# fastkey_-_v1_1.net
KiCad netlist of a schematic drawn in EAGLE
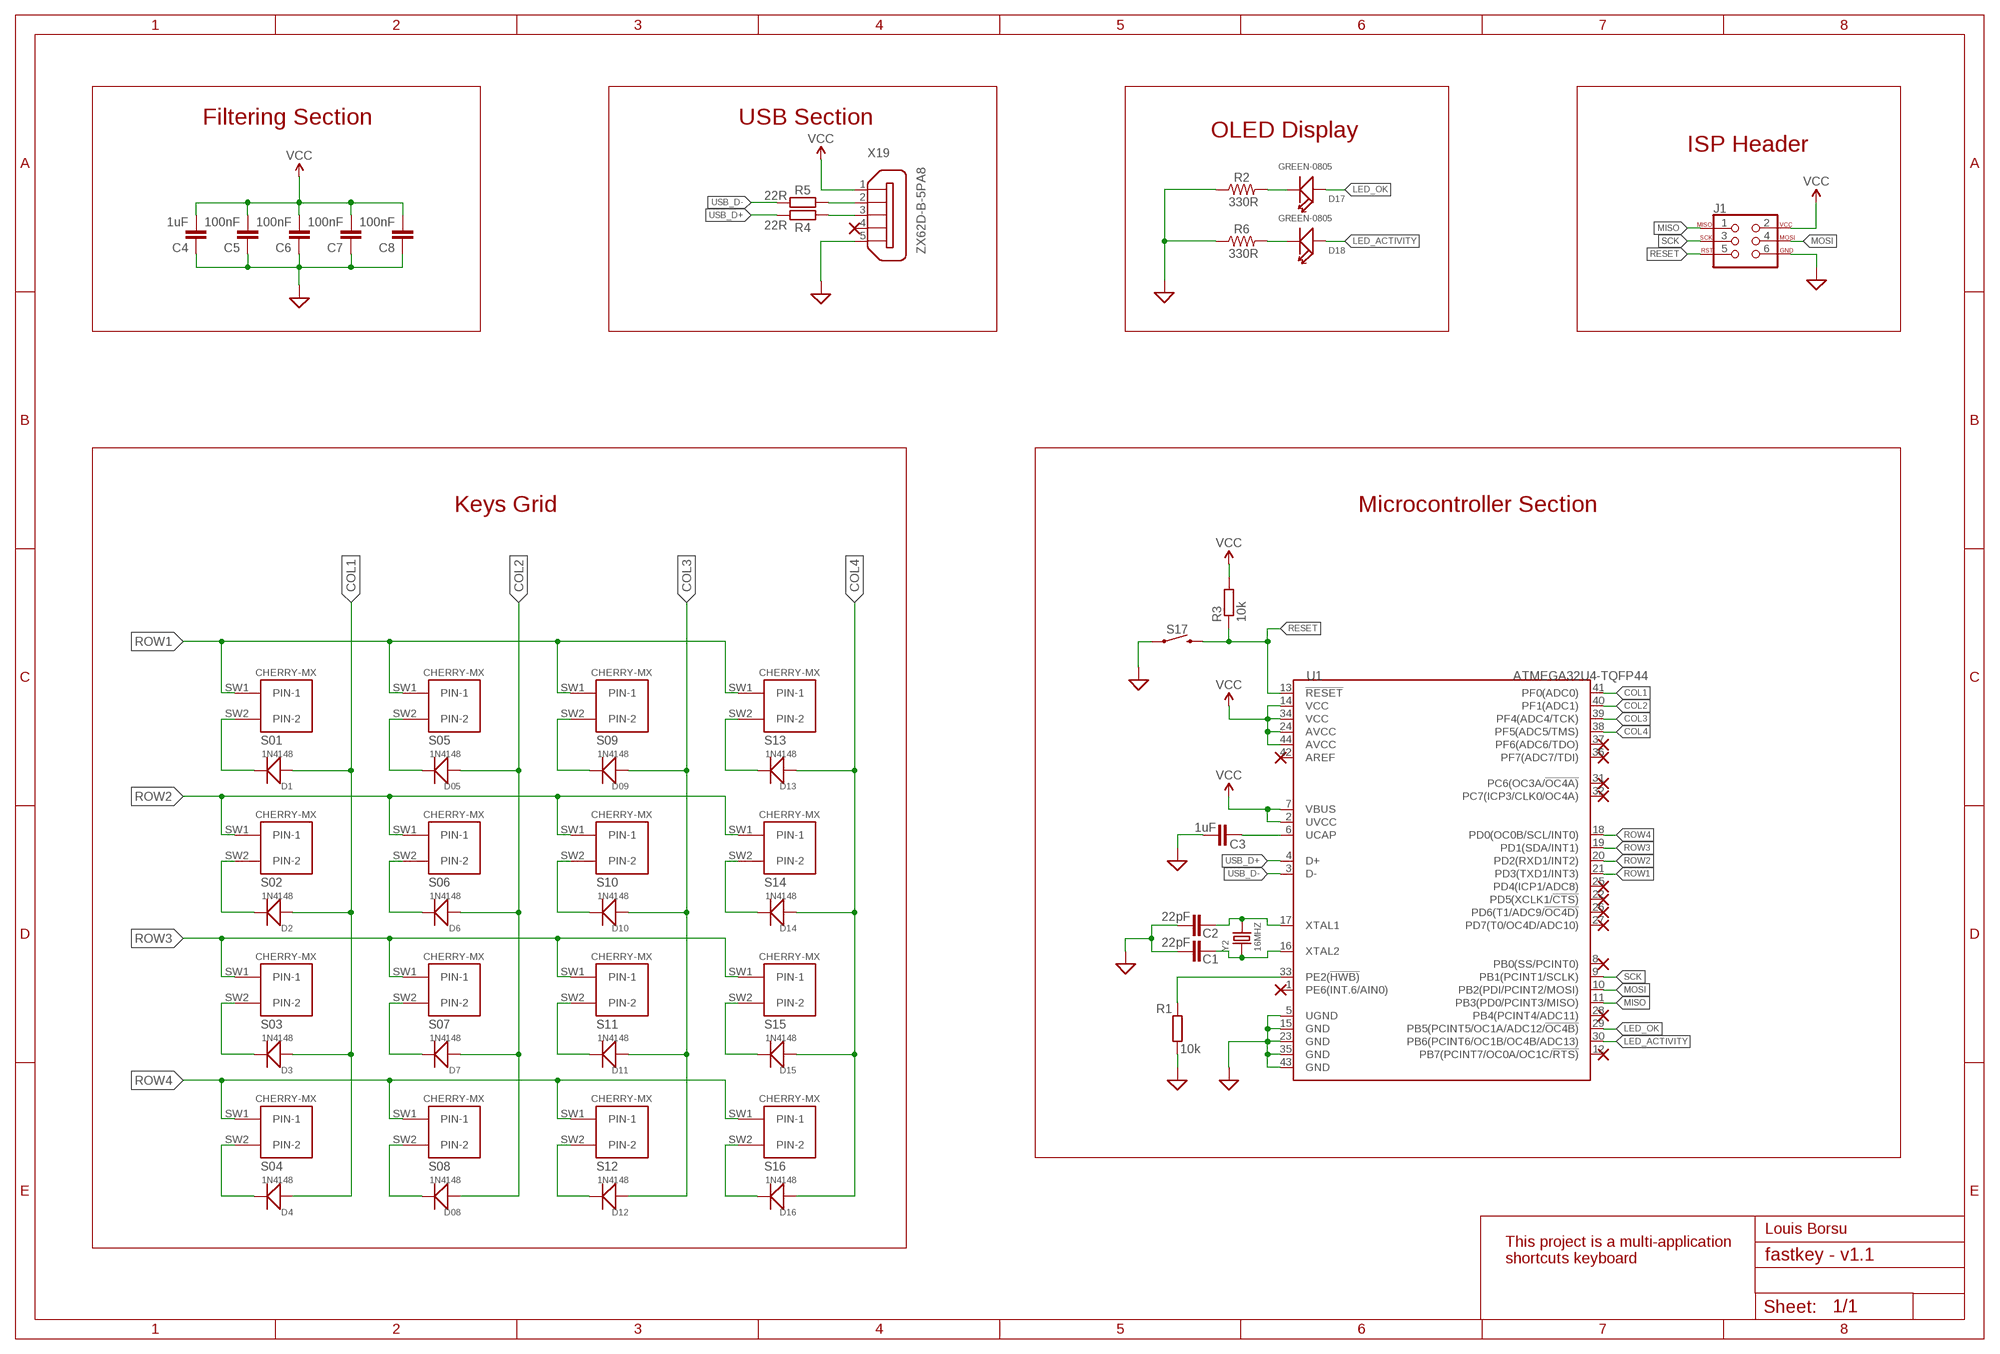
[diagram p0: schematic, sheet 1]

(export (version "E")
  (design (tool "Eeschema 10.0.6"))
  (components
    (comp (ref "C1")
      (value "22pF")
      (footprint "eagle-import:RESC0805_M")
      (libsource (lib "eagle-import") (part "CAPACITOR_0805_M"))
    )
    (comp (ref "C2")
      (value "22pF")
      (footprint "eagle-import:RESC0805_M")
      (libsource (lib "eagle-import") (part "CAPACITOR_0805_M"))
    )
    (comp (ref "C3")
      (value "1uF")
      (footprint "eagle-import:RESC0805_M")
      (libsource (lib "eagle-import") (part "CAPACITOR_0805_M"))
    )
    (comp (ref "C4")
      (value "1uF")
      (footprint "eagle-import:RESC0805_M")
      (libsource (lib "eagle-import") (part "CAPACITOR_0805_M"))
    )
    (comp (ref "C5")
      (value "100nF")
      (footprint "eagle-import:RESC0805_M")
      (libsource (lib "eagle-import") (part "CAPACITOR_0805_M"))
    )
    (comp (ref "C6")
      (value "100nF")
      (footprint "eagle-import:RESC0805_M")
      (libsource (lib "eagle-import") (part "CAPACITOR_0805_M"))
    )
    (comp (ref "C7")
      (value "100nF")
      (footprint "eagle-import:RESC0805_M")
      (libsource (lib "eagle-import") (part "CAPACITOR_0805_M"))
    )
    (comp (ref "C8")
      (value "100nF")
      (footprint "eagle-import:RESC0805_M")
      (libsource (lib "eagle-import") (part "CAPACITOR_0805_M"))
    )
    (comp (ref "D1")
      (value "1N4148")
      (footprint "eagle-import:LL-34")
      (libsource (lib "eagle-import") (part "SMD-DIODE-SWITCH-1N4148(LL-34)"))
    )
    (comp (ref "D2")
      (value "1N4148")
      (footprint "eagle-import:LL-34")
      (libsource (lib "eagle-import") (part "SMD-DIODE-SWITCH-1N4148(LL-34)"))
    )
    (comp (ref "D3")
      (value "1N4148")
      (footprint "eagle-import:LL-34")
      (libsource (lib "eagle-import") (part "SMD-DIODE-SWITCH-1N4148(LL-34)"))
    )
    (comp (ref "D4")
      (value "1N4148")
      (footprint "eagle-import:LL-34")
      (libsource (lib "eagle-import") (part "SMD-DIODE-SWITCH-1N4148(LL-34)"))
    )
    (comp (ref "D05")
      (value "1N4148")
      (footprint "eagle-import:LL-34")
      (libsource (lib "eagle-import") (part "SMD-DIODE-SWITCH-1N4148(LL-34)"))
    )
    (comp (ref "D6")
      (value "1N4148")
      (footprint "eagle-import:LL-34")
      (libsource (lib "eagle-import") (part "SMD-DIODE-SWITCH-1N4148(LL-34)"))
    )
    (comp (ref "D7")
      (value "1N4148")
      (footprint "eagle-import:LL-34")
      (libsource (lib "eagle-import") (part "SMD-DIODE-SWITCH-1N4148(LL-34)"))
    )
    (comp (ref "D08")
      (value "1N4148")
      (footprint "eagle-import:LL-34")
      (libsource (lib "eagle-import") (part "SMD-DIODE-SWITCH-1N4148(LL-34)"))
    )
    (comp (ref "D09")
      (value "1N4148")
      (footprint "eagle-import:LL-34")
      (libsource (lib "eagle-import") (part "SMD-DIODE-SWITCH-1N4148(LL-34)"))
    )
    (comp (ref "D10")
      (value "1N4148")
      (footprint "eagle-import:LL-34")
      (libsource (lib "eagle-import") (part "SMD-DIODE-SWITCH-1N4148(LL-34)"))
    )
    (comp (ref "D11")
      (value "1N4148")
      (footprint "eagle-import:LL-34")
      (libsource (lib "eagle-import") (part "SMD-DIODE-SWITCH-1N4148(LL-34)"))
    )
    (comp (ref "D12")
      (value "1N4148")
      (footprint "eagle-import:LL-34")
      (libsource (lib "eagle-import") (part "SMD-DIODE-SWITCH-1N4148(LL-34)"))
    )
    (comp (ref "D13")
      (value "1N4148")
      (footprint "eagle-import:LL-34")
      (libsource (lib "eagle-import") (part "SMD-DIODE-SWITCH-1N4148(LL-34)"))
    )
    (comp (ref "D14")
      (value "1N4148")
      (footprint "eagle-import:LL-34")
      (libsource (lib "eagle-import") (part "SMD-DIODE-SWITCH-1N4148(LL-34)"))
    )
    (comp (ref "D15")
      (value "1N4148")
      (footprint "eagle-import:LL-34")
      (libsource (lib "eagle-import") (part "SMD-DIODE-SWITCH-1N4148(LL-34)"))
    )
    (comp (ref "D16")
      (value "1N4148")
      (footprint "eagle-import:LL-34")
      (libsource (lib "eagle-import") (part "SMD-DIODE-SWITCH-1N4148(LL-34)"))
    )
    (comp (ref "D17")
      (value "GREEN-0805")
      (footprint "eagle-import:LED-0805")
      (fields (field (name "MPN") "17-215SYGC/S530-E2/TR8"))
      (libsource (lib "eagle-import") (part "SMD-LED-CLEAR-GREEN(0805)"))
    )
    (comp (ref "D18")
      (value "GREEN-0805")
      (footprint "eagle-import:LED-0805")
      (fields (field (name "MPN") "17-215SYGC/S530-E2/TR8"))
      (libsource (lib "eagle-import") (part "SMD-LED-CLEAR-GREEN(0805)"))
    )
    (comp (ref "J1")
      (value "AVR_SPI_PROG_3X22X3_LOCK")
      (footprint "eagle-import:2X3_LOCK")
      (libsource (lib "eagle-import") (part "AVR_SPI_PROG_3X22X3_LOCK"))
    )
    (comp (ref "R1")
      (value "10k")
      (footprint "eagle-import:R0805")
      (libsource (lib "eagle-import") (part "R-EU_R0805"))
    )
    (comp (ref "R2")
      (value "330R")
      (footprint "eagle-import:0805")
      (libsource (lib "eagle-import") (part "RESISTOR0805"))
    )
    (comp (ref "R3")
      (value "10k")
      (footprint "eagle-import:R0805")
      (libsource (lib "eagle-import") (part "R-EU_R0805"))
    )
    (comp (ref "R4")
      (value "22R")
      (footprint "eagle-import:R0805")
      (libsource (lib "eagle-import") (part "R-EU_R0805"))
    )
    (comp (ref "R5")
      (value "22R")
      (footprint "eagle-import:R0805")
      (libsource (lib "eagle-import") (part "R-EU_R0805"))
    )
    (comp (ref "R6")
      (value "330R")
      (footprint "eagle-import:0805")
      (libsource (lib "eagle-import") (part "RESISTOR0805"))
    )
    (comp (ref "S01")
      (value "CHERRY-MX")
      (footprint "eagle-import:CHERRY-MX")
      (libsource (lib "eagle-import") (part "CHERRY-MX"))
    )
    (comp (ref "S02")
      (value "CHERRY-MX")
      (footprint "eagle-import:CHERRY-MX")
      (libsource (lib "eagle-import") (part "CHERRY-MX"))
    )
    (comp (ref "S03")
      (value "CHERRY-MX")
      (footprint "eagle-import:CHERRY-MX")
      (libsource (lib "eagle-import") (part "CHERRY-MX"))
    )
    (comp (ref "S04")
      (value "CHERRY-MX")
      (footprint "eagle-import:CHERRY-MX")
      (libsource (lib "eagle-import") (part "CHERRY-MX"))
    )
    (comp (ref "S05")
      (value "CHERRY-MX")
      (footprint "eagle-import:CHERRY-MX")
      (libsource (lib "eagle-import") (part "CHERRY-MX"))
    )
    (comp (ref "S06")
      (value "CHERRY-MX")
      (footprint "eagle-import:CHERRY-MX")
      (libsource (lib "eagle-import") (part "CHERRY-MX"))
    )
    (comp (ref "S07")
      (value "CHERRY-MX")
      (footprint "eagle-import:CHERRY-MX")
      (libsource (lib "eagle-import") (part "CHERRY-MX"))
    )
    (comp (ref "S08")
      (value "CHERRY-MX")
      (footprint "eagle-import:CHERRY-MX")
      (libsource (lib "eagle-import") (part "CHERRY-MX"))
    )
    (comp (ref "S09")
      (value "CHERRY-MX")
      (footprint "eagle-import:CHERRY-MX")
      (libsource (lib "eagle-import") (part "CHERRY-MX"))
    )
    (comp (ref "S10")
      (value "CHERRY-MX")
      (footprint "eagle-import:CHERRY-MX")
      (libsource (lib "eagle-import") (part "CHERRY-MX"))
    )
    (comp (ref "S11")
      (value "CHERRY-MX")
      (footprint "eagle-import:CHERRY-MX")
      (libsource (lib "eagle-import") (part "CHERRY-MX"))
    )
    (comp (ref "S12")
      (value "CHERRY-MX")
      (footprint "eagle-import:CHERRY-MX")
      (libsource (lib "eagle-import") (part "CHERRY-MX"))
    )
    (comp (ref "S13")
      (value "CHERRY-MX")
      (footprint "eagle-import:CHERRY-MX")
      (libsource (lib "eagle-import") (part "CHERRY-MX"))
    )
    (comp (ref "S14")
      (value "CHERRY-MX")
      (footprint "eagle-import:CHERRY-MX")
      (libsource (lib "eagle-import") (part "CHERRY-MX"))
    )
    (comp (ref "S15")
      (value "CHERRY-MX")
      (footprint "eagle-import:CHERRY-MX")
      (libsource (lib "eagle-import") (part "CHERRY-MX"))
    )
    (comp (ref "S16")
      (value "CHERRY-MX")
      (footprint "eagle-import:CHERRY-MX")
      (libsource (lib "eagle-import") (part "CHERRY-MX"))
    )
    (comp (ref "S17")
      (value "MOMENTARY-SWITCH-SPST-SMD-6.2MM-TALL")
      (footprint "eagle-import:TACTILE_SWITCH_SMD_6.2MM_TALL")
      (libsource (lib "eagle-import") (part "MOMENTARY-SWITCH-SPST-SMD-6.2MM-TALL"))
    )
    (comp (ref "U1")
      (value "ATMEGA32U4-TQFP44")
      (footprint "eagle-import:TQFP44-0.8-9.6X9.6MM")
      (fields (field (name "MPN") "ATMEGA32U4"))
      (libsource (lib "eagle-import") (part "MCU-ATMEGA32U4-AU(TQFP44)"))
    )
    (comp (ref "X19")
      (value "ZX62D-B-5PA8")
      (footprint "eagle-import:ZX62D-B-5PA8")
      (fields (field (name "MF") "Hirose"))
      (libsource (lib "eagle-import") (part "ZX62D-B-5PA8"))
    )
    (comp (ref "Y2")
      (value "16MHZ")
      (footprint "eagle-import:X2-SMD-5.0X3.2X1.3MM")
      (fields (field (name "MPN") "X053201602002"))
      (libsource (lib "eagle-import") (part "SMD-CRYSTAL-16MHZ-8PF-20PPM-40R(2P-5.0X3.2MM)"))
    )
  )
  (nets
    (net (code "1") (name "COL1") (class "Default")
      (node (ref "D1") (pin "A") (pinfunction "+_A") (pintype "passive"))
      (node (ref "D2") (pin "A") (pinfunction "+_A") (pintype "passive"))
      (node (ref "D3") (pin "A") (pinfunction "+_A") (pintype "passive"))
      (node (ref "D4") (pin "A") (pinfunction "+_A") (pintype "passive"))
      (node (ref "U1") (pin "41") (pinfunction "PF0(ADC0)_41") (pintype "bidirectional"))
    )
    (net (code "2") (name "COL2") (class "Default")
      (node (ref "D05") (pin "A") (pinfunction "+_A") (pintype "passive"))
      (node (ref "D08") (pin "A") (pinfunction "+_A") (pintype "passive"))
      (node (ref "D6") (pin "A") (pinfunction "+_A") (pintype "passive"))
      (node (ref "D7") (pin "A") (pinfunction "+_A") (pintype "passive"))
      (node (ref "U1") (pin "40") (pinfunction "PF1(ADC1)_40") (pintype "bidirectional"))
    )
    (net (code "3") (name "COL3") (class "Default")
      (node (ref "D09") (pin "A") (pinfunction "+_A") (pintype "passive"))
      (node (ref "D10") (pin "A") (pinfunction "+_A") (pintype "passive"))
      (node (ref "D11") (pin "A") (pinfunction "+_A") (pintype "passive"))
      (node (ref "D12") (pin "A") (pinfunction "+_A") (pintype "passive"))
      (node (ref "U1") (pin "39") (pinfunction "PF4(ADC4/TCK)_39") (pintype "bidirectional"))
    )
    (net (code "4") (name "COL4") (class "Default")
      (node (ref "D13") (pin "A") (pinfunction "+_A") (pintype "passive"))
      (node (ref "D14") (pin "A") (pinfunction "+_A") (pintype "passive"))
      (node (ref "D15") (pin "A") (pinfunction "+_A") (pintype "passive"))
      (node (ref "D16") (pin "A") (pinfunction "+_A") (pintype "passive"))
      (node (ref "U1") (pin "38") (pinfunction "PF5(ADC5/TMS)_38") (pintype "bidirectional"))
    )
    (net (code "5") (name "LED_ACTIVITY") (class "Default")
      (node (ref "D18") (pin "+") (pinfunction "+_+") (pintype "passive"))
      (node (ref "U1") (pin "30") (pinfunction "PB6(PCINT6/OC1B/OC4B/ADC13)_30") (pintype "bidirectional"))
    )
    (net (code "6") (name "LED_OK") (class "Default")
      (node (ref "D17") (pin "+") (pinfunction "+_+") (pintype "passive"))
      (node (ref "U1") (pin "29") (pinfunction "PB5(PCINT5/OC1A/ADC12/~{OC4B})_29") (pintype "bidirectional"))
    )
    (net (code "7") (name "MISO") (class "Default")
      (node (ref "J1") (pin "1") (pinfunction "1_1") (pintype "passive"))
      (node (ref "U1") (pin "11") (pinfunction "PB3(PD0/PCINT3/MISO)_11") (pintype "bidirectional"))
    )
    (net (code "8") (name "MOSI") (class "Default")
      (node (ref "J1") (pin "4") (pinfunction "4_4") (pintype "passive"))
      (node (ref "U1") (pin "10") (pinfunction "PB2(PDI/PCINT2/MOSI)_10") (pintype "bidirectional"))
    )
    (net (code "9") (name "Net-(D1--)") (class "Default")
      (node (ref "D1") (pin "C") (pinfunction "-_C") (pintype "passive"))
      (node (ref "S01") (pin "SW2") (pinfunction "PIN-2_SW2") (pintype "bidirectional"))
    )
    (net (code "10") (name "Net-(D2--)") (class "Default")
      (node (ref "D2") (pin "C") (pinfunction "-_C") (pintype "passive"))
      (node (ref "S02") (pin "SW2") (pinfunction "PIN-2_SW2") (pintype "bidirectional"))
    )
    (net (code "11") (name "Net-(D3--)") (class "Default")
      (node (ref "D3") (pin "C") (pinfunction "-_C") (pintype "passive"))
      (node (ref "S03") (pin "SW2") (pinfunction "PIN-2_SW2") (pintype "bidirectional"))
    )
    (net (code "12") (name "Net-(D4--)") (class "Default")
      (node (ref "D4") (pin "C") (pinfunction "-_C") (pintype "passive"))
      (node (ref "S04") (pin "SW2") (pinfunction "PIN-2_SW2") (pintype "bidirectional"))
    )
    (net (code "13") (name "Net-(D05--)") (class "Default")
      (node (ref "D05") (pin "C") (pinfunction "-_C") (pintype "passive"))
      (node (ref "S05") (pin "SW2") (pinfunction "PIN-2_SW2") (pintype "bidirectional"))
    )
    (net (code "14") (name "Net-(D6--)") (class "Default")
      (node (ref "D6") (pin "C") (pinfunction "-_C") (pintype "passive"))
      (node (ref "S06") (pin "SW2") (pinfunction "PIN-2_SW2") (pintype "bidirectional"))
    )
    (net (code "15") (name "Net-(D7--)") (class "Default")
      (node (ref "D7") (pin "C") (pinfunction "-_C") (pintype "passive"))
      (node (ref "S07") (pin "SW2") (pinfunction "PIN-2_SW2") (pintype "bidirectional"))
    )
    (net (code "16") (name "Net-(D08--)") (class "Default")
      (node (ref "D08") (pin "C") (pinfunction "-_C") (pintype "passive"))
      (node (ref "S08") (pin "SW2") (pinfunction "PIN-2_SW2") (pintype "bidirectional"))
    )
    (net (code "17") (name "Net-(D09--)") (class "Default")
      (node (ref "D09") (pin "C") (pinfunction "-_C") (pintype "passive"))
      (node (ref "S09") (pin "SW2") (pinfunction "PIN-2_SW2") (pintype "bidirectional"))
    )
    (net (code "18") (name "Net-(D10--)") (class "Default")
      (node (ref "D10") (pin "C") (pinfunction "-_C") (pintype "passive"))
      (node (ref "S10") (pin "SW2") (pinfunction "PIN-2_SW2") (pintype "bidirectional"))
    )
    (net (code "19") (name "Net-(D11--)") (class "Default")
      (node (ref "D11") (pin "C") (pinfunction "-_C") (pintype "passive"))
      (node (ref "S11") (pin "SW2") (pinfunction "PIN-2_SW2") (pintype "bidirectional"))
    )
    (net (code "20") (name "Net-(D12--)") (class "Default")
      (node (ref "D12") (pin "C") (pinfunction "-_C") (pintype "passive"))
      (node (ref "S12") (pin "SW2") (pinfunction "PIN-2_SW2") (pintype "bidirectional"))
    )
    (net (code "21") (name "Net-(D13--)") (class "Default")
      (node (ref "D13") (pin "C") (pinfunction "-_C") (pintype "passive"))
      (node (ref "S13") (pin "SW2") (pinfunction "PIN-2_SW2") (pintype "bidirectional"))
    )
    (net (code "22") (name "Net-(D14--)") (class "Default")
      (node (ref "D14") (pin "C") (pinfunction "-_C") (pintype "passive"))
      (node (ref "S14") (pin "SW2") (pinfunction "PIN-2_SW2") (pintype "bidirectional"))
    )
    (net (code "23") (name "Net-(D15--)") (class "Default")
      (node (ref "D15") (pin "C") (pinfunction "-_C") (pintype "passive"))
      (node (ref "S15") (pin "SW2") (pinfunction "PIN-2_SW2") (pintype "bidirectional"))
    )
    (net (code "24") (name "Net-(D16--)") (class "Default")
      (node (ref "D16") (pin "C") (pinfunction "-_C") (pintype "passive"))
      (node (ref "S16") (pin "SW2") (pinfunction "PIN-2_SW2") (pintype "bidirectional"))
    )
    (net (code "25") (name "Net-(D17-Pad-)") (class "Default")
      (node (ref "D17") (pin "-") (pinfunction "-_-") (pintype "passive"))
      (node (ref "R2") (pin "2") (pinfunction "2_2") (pintype "passive"))
    )
    (net (code "26") (name "Net-(D18-Pad-)") (class "Default")
      (node (ref "D18") (pin "-") (pinfunction "-_-") (pintype "passive"))
      (node (ref "R6") (pin "2") (pinfunction "2_2") (pintype "passive"))
    )
    (net (code "27") (name "Net-(R4-Pad1)") (class "Default")
      (node (ref "R4") (pin "1") (pinfunction "1_1") (pintype "passive"))
      (node (ref "X19") (pin "3") (pinfunction "3_3") (pintype "passive"))
    )
    (net (code "28") (name "Net-(R5-Pad1)") (class "Default")
      (node (ref "R5") (pin "1") (pinfunction "1_1") (pintype "passive"))
      (node (ref "X19") (pin "2") (pinfunction "2_2") (pintype "passive"))
    )
    (net (code "29") (name "Net-(U1-PE2(~{HWB}))") (class "Default")
      (node (ref "R1") (pin "2") (pinfunction "2_2") (pintype "passive"))
      (node (ref "U1") (pin "33") (pinfunction "PE2(~{HWB})_33") (pintype "bidirectional"))
    )
    (net (code "30") (name "Net-(U1-UCAP)") (class "Default")
      (node (ref "C3") (pin "2") (pinfunction "2_2") (pintype "passive"))
      (node (ref "U1") (pin "6") (pinfunction "UCAP_6") (pintype "bidirectional"))
    )
    (net (code "31") (name "Net-(U1-XTAL1)") (class "Default")
      (node (ref "C2") (pin "2") (pinfunction "2_2") (pintype "passive"))
      (node (ref "U1") (pin "17") (pinfunction "XTAL1_17") (pintype "bidirectional"))
      (node (ref "Y2") (pin "2") (pinfunction "2_2") (pintype "passive"))
    )
    (net (code "32") (name "Net-(U1-XTAL2)") (class "Default")
      (node (ref "C1") (pin "2") (pinfunction "2_2") (pintype "passive"))
      (node (ref "U1") (pin "16") (pinfunction "XTAL2_16") (pintype "bidirectional"))
      (node (ref "Y2") (pin "1") (pinfunction "1_1") (pintype "passive"))
    )
    (net (code "33") (name "RESET") (class "Default")
      (node (ref "J1") (pin "5") (pinfunction "5_5") (pintype "passive"))
      (node (ref "R3") (pin "1") (pinfunction "1_1") (pintype "passive"))
      (node (ref "S17") (pin "B2") (pinfunction "2_B2") (pintype "passive"))
      (node (ref "U1") (pin "13") (pinfunction "~{RESET}_13") (pintype "bidirectional"))
    )
    (net (code "34") (name "ROW1") (class "Default")
      (node (ref "S01") (pin "SW1") (pinfunction "PIN-1_SW1") (pintype "bidirectional"))
      (node (ref "S05") (pin "SW1") (pinfunction "PIN-1_SW1") (pintype "bidirectional"))
      (node (ref "S09") (pin "SW1") (pinfunction "PIN-1_SW1") (pintype "bidirectional"))
      (node (ref "S13") (pin "SW1") (pinfunction "PIN-1_SW1") (pintype "bidirectional"))
      (node (ref "U1") (pin "21") (pinfunction "PD3(TXD1/INT3)_21") (pintype "bidirectional"))
    )
    (net (code "35") (name "ROW2") (class "Default")
      (node (ref "S02") (pin "SW1") (pinfunction "PIN-1_SW1") (pintype "bidirectional"))
      (node (ref "S06") (pin "SW1") (pinfunction "PIN-1_SW1") (pintype "bidirectional"))
      (node (ref "S10") (pin "SW1") (pinfunction "PIN-1_SW1") (pintype "bidirectional"))
      (node (ref "S14") (pin "SW1") (pinfunction "PIN-1_SW1") (pintype "bidirectional"))
      (node (ref "U1") (pin "20") (pinfunction "PD2(RXD1/INT2)_20") (pintype "bidirectional"))
    )
    (net (code "36") (name "ROW3") (class "Default")
      (node (ref "S03") (pin "SW1") (pinfunction "PIN-1_SW1") (pintype "bidirectional"))
      (node (ref "S07") (pin "SW1") (pinfunction "PIN-1_SW1") (pintype "bidirectional"))
      (node (ref "S11") (pin "SW1") (pinfunction "PIN-1_SW1") (pintype "bidirectional"))
      (node (ref "S15") (pin "SW1") (pinfunction "PIN-1_SW1") (pintype "bidirectional"))
      (node (ref "U1") (pin "19") (pinfunction "PD1(SDA/INT1)_19") (pintype "bidirectional"))
    )
    (net (code "37") (name "ROW4") (class "Default")
      (node (ref "S04") (pin "SW1") (pinfunction "PIN-1_SW1") (pintype "bidirectional"))
      (node (ref "S08") (pin "SW1") (pinfunction "PIN-1_SW1") (pintype "bidirectional"))
      (node (ref "S12") (pin "SW1") (pinfunction "PIN-1_SW1") (pintype "bidirectional"))
      (node (ref "S16") (pin "SW1") (pinfunction "PIN-1_SW1") (pintype "bidirectional"))
      (node (ref "U1") (pin "18") (pinfunction "PD0(OC0B/SCL/INT0)_18") (pintype "bidirectional"))
    )
    (net (code "38") (name "SCK") (class "Default")
      (node (ref "J1") (pin "3") (pinfunction "3_3") (pintype "passive"))
      (node (ref "U1") (pin "9") (pinfunction "PB1(PCINT1/SCLK)_9") (pintype "bidirectional"))
    )
    (net (code "39") (name "SUP") (class "Default")
      (node (ref "C1") (pin "1") (pinfunction "1_1") (pintype "passive"))
      (node (ref "C2") (pin "1") (pinfunction "1_1") (pintype "passive"))
      (node (ref "C3") (pin "1") (pinfunction "1_1") (pintype "passive"))
      (node (ref "C4") (pin "1") (pinfunction "1_1") (pintype "passive"))
      (node (ref "C5") (pin "1") (pinfunction "1_1") (pintype "passive"))
      (node (ref "C6") (pin "1") (pinfunction "1_1") (pintype "passive"))
      (node (ref "C7") (pin "1") (pinfunction "1_1") (pintype "passive"))
      (node (ref "C8") (pin "1") (pinfunction "1_1") (pintype "passive"))
      (node (ref "J1") (pin "6") (pinfunction "6_6") (pintype "passive"))
      (node (ref "R1") (pin "1") (pinfunction "1_1") (pintype "passive"))
      (node (ref "R2") (pin "1") (pinfunction "1_1") (pintype "passive"))
      (node (ref "R6") (pin "1") (pinfunction "1_1") (pintype "passive"))
      (node (ref "S17") (pin "A2") (pinfunction "1_A2") (pintype "passive"))
      (node (ref "U1") (pin "15") (pinfunction "GND_15") (pintype "bidirectional"))
      (node (ref "U1") (pin "23") (pinfunction "GND_23") (pintype "bidirectional"))
      (node (ref "U1") (pin "35") (pinfunction "GND_35") (pintype "bidirectional"))
      (node (ref "U1") (pin "43") (pinfunction "GND_43") (pintype "bidirectional"))
      (node (ref "U1") (pin "5") (pinfunction "UGND_5") (pintype "bidirectional"))
      (node (ref "X19") (pin "5") (pinfunction "5_5") (pintype "passive"))
    )
    (net (code "40") (name "USB_D+") (class "Default")
      (node (ref "R4") (pin "2") (pinfunction "2_2") (pintype "passive"))
      (node (ref "U1") (pin "4") (pinfunction "D+_4") (pintype "bidirectional"))
    )
    (net (code "41") (name "USB_D-") (class "Default")
      (node (ref "R5") (pin "2") (pinfunction "2_2") (pintype "passive"))
      (node (ref "U1") (pin "3") (pinfunction "D-_3") (pintype "bidirectional"))
    )
    (net (code "42") (name "VCC") (class "Default")
      (node (ref "C4") (pin "2") (pinfunction "2_2") (pintype "passive"))
      (node (ref "C5") (pin "2") (pinfunction "2_2") (pintype "passive"))
      (node (ref "C6") (pin "2") (pinfunction "2_2") (pintype "passive"))
      (node (ref "C7") (pin "2") (pinfunction "2_2") (pintype "passive"))
      (node (ref "C8") (pin "2") (pinfunction "2_2") (pintype "passive"))
      (node (ref "J1") (pin "2") (pinfunction "2_2") (pintype "passive"))
      (node (ref "R3") (pin "2") (pinfunction "2_2") (pintype "passive"))
      (node (ref "U1") (pin "14") (pinfunction "VCC_14") (pintype "bidirectional"))
      (node (ref "U1") (pin "2") (pinfunction "UVCC_2") (pintype "bidirectional"))
      (node (ref "U1") (pin "24") (pinfunction "AVCC_24") (pintype "bidirectional"))
      (node (ref "U1") (pin "34") (pinfunction "VCC_34") (pintype "bidirectional"))
      (node (ref "U1") (pin "44") (pinfunction "AVCC_44") (pintype "bidirectional"))
      (node (ref "U1") (pin "7") (pinfunction "VBUS_7") (pintype "bidirectional"))
      (node (ref "X19") (pin "1") (pinfunction "1_1") (pintype "passive"))
    )
    (net (code "43") (name "unconnected-(U1-AREF-Pad42)") (class "Default")
      (node (ref "U1") (pin "42") (pinfunction "AREF_42") (pintype "bidirectional"))
    )
    (net (code "44") (name "unconnected-(U1-PB0(SS{slash}PCINT0)-Pad8)") (class "Default")
      (node (ref "U1") (pin "8") (pinfunction "PB0(SS/PCINT0)_8") (pintype "bidirectional"))
    )
    (net (code "45") (name "unconnected-(U1-PB4(PCINT4{slash}ADC11)-Pad28)") (class "Default")
      (node (ref "U1") (pin "28") (pinfunction "PB4(PCINT4/ADC11)_28") (pintype "bidirectional"))
    )
    (net (code "46") (name "unconnected-(U1-PB7(PCINT7{slash}OC0A{slash}OC1C{slash}~{RTS})-Pad12)") (class "Default")
      (node (ref "U1") (pin "12") (pinfunction "PB7(PCINT7/OC0A/OC1C/~{RTS})_12") (pintype "bidirectional"))
    )
    (net (code "47") (name "unconnected-(U1-PC6(OC3A{slash}~{OC4A})-Pad31)") (class "Default")
      (node (ref "U1") (pin "31") (pinfunction "PC6(OC3A/~{OC4A})_31") (pintype "bidirectional"))
    )
    (net (code "48") (name "unconnected-(U1-PC7(ICP3{slash}CLK0{slash}OC4A)-Pad32)") (class "Default")
      (node (ref "U1") (pin "32") (pinfunction "PC7(ICP3/CLK0/OC4A)_32") (pintype "bidirectional"))
    )
    (net (code "49") (name "unconnected-(U1-PD4(ICP1{slash}ADC8)-Pad25)") (class "Default")
      (node (ref "U1") (pin "25") (pinfunction "PD4(ICP1/ADC8)_25") (pintype "bidirectional"))
    )
    (net (code "50") (name "unconnected-(U1-PD5(XCLK1{slash}~{CTS})-Pad22)") (class "Default")
      (node (ref "U1") (pin "22") (pinfunction "PD5(XCLK1/~{CTS})_22") (pintype "bidirectional"))
    )
    (net (code "51") (name "unconnected-(U1-PD6(T1{slash}ADC9{slash}~{OC4D})-Pad26)") (class "Default")
      (node (ref "U1") (pin "26") (pinfunction "PD6(T1/ADC9/~{OC4D})_26") (pintype "bidirectional"))
    )
    (net (code "52") (name "unconnected-(U1-PD7(T0{slash}OC4D{slash}ADC10)-Pad27)") (class "Default")
      (node (ref "U1") (pin "27") (pinfunction "PD7(T0/OC4D/ADC10)_27") (pintype "bidirectional"))
    )
    (net (code "53") (name "unconnected-(U1-PE6(INT.6{slash}AIN0)-Pad1)") (class "Default")
      (node (ref "U1") (pin "1") (pinfunction "PE6(INT.6/AIN0)_1") (pintype "bidirectional"))
    )
    (net (code "54") (name "unconnected-(U1-PF6(ADC6{slash}TDO)-Pad37)") (class "Default")
      (node (ref "U1") (pin "37") (pinfunction "PF6(ADC6/TDO)_37") (pintype "bidirectional"))
    )
    (net (code "55") (name "unconnected-(U1-PF7(ADC7{slash}TDI)-Pad36)") (class "Default")
      (node (ref "U1") (pin "36") (pinfunction "PF7(ADC7/TDI)_36") (pintype "bidirectional"))
    )
    (net (code "56") (name "unconnected-(X19-Pad4)") (class "Default")
      (node (ref "X19") (pin "4") (pinfunction "4_4") (pintype "passive"))
    )
  )
)
